# LDO.net
KiCad netlist of a schematic drawn in Altium Designer
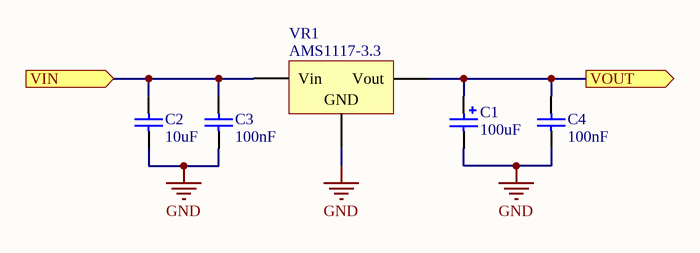
[diagram p0: LDO.SchDoc]

(export (version "E")
  (design (tool "Eeschema 10.0.6"))
  (components
    (comp (ref "C1")
      (value "100uF")
      (footprint "CASE-B_3528")
      (description "Tantalum capacitor")
      (fields (field (name "MANUFACTURER") "AVX") (field (name "PARTNUMBER") "TAJB107K006RNJ"))
      (libsource (lib "Cap") (part "3528 100uF (107) 10% 6.3V"))
    )
    (comp (ref "C2")
      (value "10uF")
      (footprint "1206_C")
      (description "Chip capacitors")
      (fields
        (field (name "MANUFACTURER") "Samsung Electro-Mechanics")
        (field (name "PARTNUMBER") "CL31A106KBHNNNE")
      )
      (libsource (lib "Cap") (part "1206 10uF (106) 10% 50V"))
    )
    (comp (ref "C3")
      (value "100nF")
      (footprint "0805_C")
      (description "Chip capacitors")
      (fields (field (name "MANUFACTURER") "YAGEO") (field (name "PARTNUMBER") "CC0805KRX7R9BB104"))
      (libsource (lib "Miscellaneous Devices LC") (part "0805 100nF(104) 10% 50V"))
    )
    (comp (ref "C4")
      (value "100nF")
      (footprint "1206_C")
      (description "Chip capacitors")
      (fields
        (field (name "MANUFACTURER") "Samsung Electro-Mechanics")
        (field (name "PARTNUMBER") "CL31B104KBCNNNC")
      )
      (libsource (lib "Miscellaneous Devices LC") (part "1206 100nF (104) 10% 50V"))
    )
    (comp (ref "VR1")
      (value "AMS1117-3.3")
      (footprint "SOT-223")
      (description "低压差线性稳压(LDO)")
      (libsource (lib "Miscellaneous Devices LC") (part "SOT-223 AMS1117-3.3"))
    )
  )
  (nets
    (net (code "1") (name "/VIN") (class "Default")
      (node (ref "C2") (pin "2") (pinfunction "2_2") (pintype "passive"))
      (node (ref "C3") (pin "2") (pinfunction "2_2") (pintype "passive"))
      (node (ref "VR1") (pin "3") (pinfunction "Vin_3") (pintype "passive"))
    )
    (net (code "2") (name "/VOUT") (class "Default")
      (node (ref "C1") (pin "1") (pinfunction "1_1") (pintype "passive"))
      (node (ref "C4") (pin "2") (pinfunction "2_2") (pintype "passive"))
      (node (ref "VR1") (pin "2") (pinfunction "Vout_2") (pintype "passive"))
    )
    (net (code "3") (name "GND") (class "Default")
      (node (ref "C1") (pin "2") (pinfunction "2_2") (pintype "passive"))
      (node (ref "C2") (pin "1") (pinfunction "1_1") (pintype "passive"))
      (node (ref "C3") (pin "1") (pinfunction "1_1") (pintype "passive"))
      (node (ref "C4") (pin "1") (pinfunction "1_1") (pintype "passive"))
      (node (ref "VR1") (pin "1") (pinfunction "GND_1") (pintype "passive"))
    )
  )
)
